# 11-GPS.net
KiCad netlist of a schematic drawn in Altium Designer
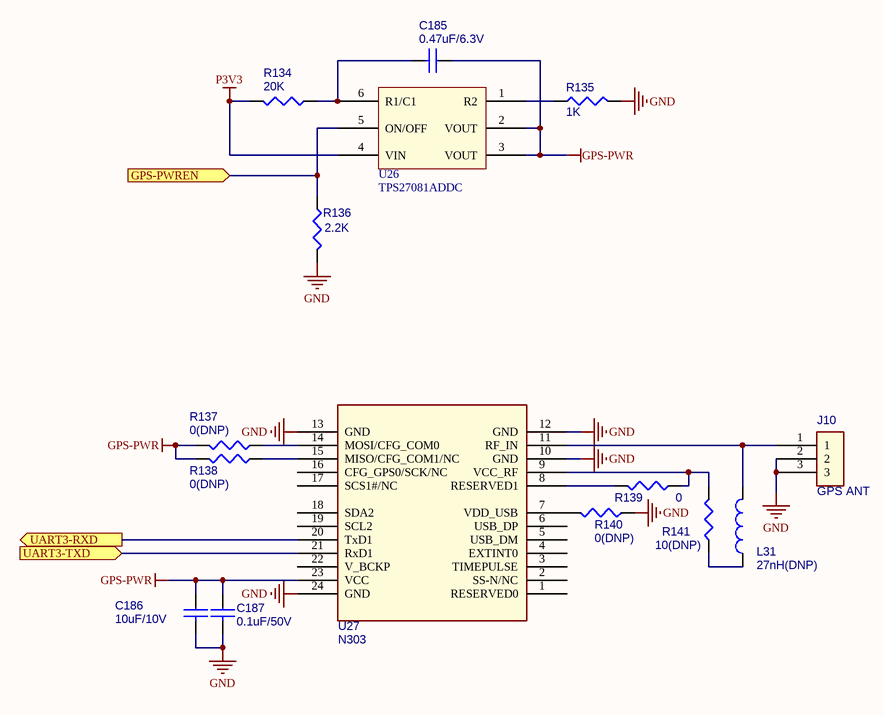
[diagram p0: 11-GPS.SchDoc]

(export (version "E")
  (design (tool "Eeschema 10.0.6"))
  (components
    (comp (ref "C185") (value "0.47uF/6.3V") (footprint "0402") (libsource (lib "*") (part "P_CAP NP")))
    (comp (ref "C186") (value "10uF/10V") (libsource (lib "*") (part "P_CAP NP")))
    (comp (ref "C187") (value "0.1uF/50V") (libsource (lib "*") (part "P_CAP NP")))
    (comp (ref "J10") (value "GPS ANT") (footprint "ANT") (libsource (lib "*") (part "HRS_U_0.FL-R-SMT-10")))
    (comp (ref "L31")
      (value "27nH(DNP)")
      (footprint "0603")
      (libsource (lib "*") (part "2.2UH_LPS3015-222MLC_1.5A_20%~D"))
    )
    (comp (ref "R134") (value "20K") (footprint "0402") (libsource (lib "*") (part "P_R")))
    (comp (ref "R135") (value "1K") (footprint "0402") (libsource (lib "*") (part "P_R")))
    (comp (ref "R136") (value "2.2K") (footprint "0402") (libsource (lib "*") (part "P_R")))
    (comp (ref "R137") (value "0(DNP)") (footprint "0402") (libsource (lib "*") (part "P_R")))
    (comp (ref "R138") (value "0(DNP)") (footprint "0402") (libsource (lib "*") (part "P_R")))
    (comp (ref "R139") (value "0") (footprint "0402") (libsource (lib "*") (part "P_R")))
    (comp (ref "R140") (value "0(DNP)") (footprint "0402") (libsource (lib "*") (part "P_R")))
    (comp (ref "R141") (value "10(DNP)") (footprint "0402") (libsource (lib "*") (part "P_R")))
    (comp (ref "U26")
      (value "TPS27081ADDC")
      (footprint "SOT23-6")
      (libsource (lib "Schlib") (part "TPS27081A"))
    )
    (comp (ref "U27") (value "N303") (footprint "NEO-6") (libsource (lib "*") (part "NEO-5M")))
  )
  (nets
    (net (code "1") (name "/GPS-PWREN") (class "Default")
      (node (ref "R136") (pin "2") (pinfunction "2_2") (pintype "passive"))
      (node (ref "U26") (pin "5") (pinfunction "ON/OFF_5") (pintype "passive"))
    )
    (net (code "2") (name "/UART3-RXD") (class "Default")
      (node (ref "U27") (pin "20") (pinfunction "TxD1_20") (pintype "passive"))
    )
    (net (code "3") (name "/UART3-TXD") (class "Default")
      (node (ref "U27") (pin "21") (pinfunction "RxD1_21") (pintype "passive"))
    )
    (net (code "4") (name "GND") (class "Default")
      (node (ref "C186") (pin "2") (pinfunction "2_2") (pintype "passive"))
      (node (ref "C187") (pin "2") (pinfunction "2_2") (pintype "passive"))
      (node (ref "J10") (pin "2") (pinfunction "2_2") (pintype "passive"))
      (node (ref "J10") (pin "3") (pinfunction "3_3") (pintype "passive"))
      (node (ref "R135") (pin "1") (pinfunction "1_1") (pintype "passive"))
      (node (ref "R136") (pin "1") (pinfunction "1_1") (pintype "passive"))
      (node (ref "R140") (pin "1") (pinfunction "1_1") (pintype "passive"))
      (node (ref "U27") (pin "10") (pinfunction "GND_10") (pintype "power_in"))
      (node (ref "U27") (pin "12") (pinfunction "GND_12") (pintype "power_in"))
      (node (ref "U27") (pin "13") (pinfunction "GND_13") (pintype "power_in"))
      (node (ref "U27") (pin "24") (pinfunction "GND_24") (pintype "power_in"))
    )
    (net (code "5") (name "GPS-PWR") (class "Default")
      (node (ref "C185") (pin "1") (pinfunction "1_1") (pintype "passive"))
      (node (ref "C186") (pin "1") (pinfunction "1_1") (pintype "passive"))
      (node (ref "C187") (pin "1") (pinfunction "1_1") (pintype "passive"))
      (node (ref "R137") (pin "2") (pinfunction "2_2") (pintype "passive"))
      (node (ref "R138") (pin "2") (pinfunction "2_2") (pintype "passive"))
      (node (ref "U26") (pin "2") (pinfunction "VOUT_2") (pintype "passive"))
      (node (ref "U26") (pin "3") (pinfunction "VOUT_3") (pintype "passive"))
      (node (ref "U27") (pin "23") (pinfunction "VCC_23") (pintype "passive"))
    )
    (net (code "6") (name "Net-(L31-Pad1)") (class "Default")
      (node (ref "L31") (pin "1") (pinfunction "1_1") (pintype "passive"))
      (node (ref "R141") (pin "1") (pinfunction "1_1") (pintype "passive"))
    )
    (net (code "7") (name "Net-(U26-R1{slash}C1)") (class "Default")
      (node (ref "C185") (pin "2") (pinfunction "2_2") (pintype "passive"))
      (node (ref "R134") (pin "2") (pinfunction "2_2") (pintype "passive"))
      (node (ref "U26") (pin "6") (pinfunction "R1/C1_6") (pintype "passive"))
    )
    (net (code "8") (name "Net-(U26-R2)") (class "Default")
      (node (ref "R135") (pin "2") (pinfunction "2_2") (pintype "passive"))
      (node (ref "U26") (pin "1") (pinfunction "R2_1") (pintype "passive"))
    )
    (net (code "9") (name "Net-(U27-MISO{slash}CFG_COM1{slash}NC)") (class "Default")
      (node (ref "R138") (pin "1") (pinfunction "1_1") (pintype "passive"))
      (node (ref "U27") (pin "15") (pinfunction "MISO/CFG_COM1/NC_15") (pintype "passive"))
    )
    (net (code "10") (name "Net-(U27-MOSI{slash}CFG_COM0)") (class "Default")
      (node (ref "R137") (pin "1") (pinfunction "1_1") (pintype "passive"))
      (node (ref "U27") (pin "14") (pinfunction "MOSI/CFG_COM0_14") (pintype "passive"))
    )
    (net (code "11") (name "Net-(U27-RESERVED1)") (class "Default")
      (node (ref "R139") (pin "2") (pinfunction "2_2") (pintype "passive"))
      (node (ref "U27") (pin "8") (pinfunction "RESERVED1_8") (pintype "passive"))
    )
    (net (code "12") (name "Net-(U27-RF_IN)") (class "Default")
      (node (ref "J10") (pin "1") (pinfunction "1_1") (pintype "passive"))
      (node (ref "L31") (pin "2") (pinfunction "2_2") (pintype "passive"))
      (node (ref "U27") (pin "11") (pinfunction "RF_IN_11") (pintype "passive"))
    )
    (net (code "13") (name "Net-(U27-VCC_RF)") (class "Default")
      (node (ref "R139") (pin "1") (pinfunction "1_1") (pintype "passive"))
      (node (ref "R141") (pin "2") (pinfunction "2_2") (pintype "passive"))
      (node (ref "U27") (pin "9") (pinfunction "VCC_RF_9") (pintype "passive"))
    )
    (net (code "14") (name "Net-(U27-VDD_USB)") (class "Default")
      (node (ref "R140") (pin "2") (pinfunction "2_2") (pintype "passive"))
      (node (ref "U27") (pin "7") (pinfunction "VDD_USB_7") (pintype "passive"))
    )
    (net (code "15") (name "P3V3") (class "Default")
      (node (ref "R134") (pin "1") (pinfunction "1_1") (pintype "passive"))
      (node (ref "U26") (pin "4") (pinfunction "VIN_4") (pintype "passive"))
    )
    (net (code "16") (name "unconnected-(U27-CFG_GPS0{slash}SCK{slash}NC-Pad16)") (class "Default")
      (node (ref "U27") (pin "16") (pinfunction "CFG_GPS0/SCK/NC_16") (pintype "passive"))
    )
    (net (code "17") (name "unconnected-(U27-EXTINT0-Pad4)") (class "Default")
      (node (ref "U27") (pin "4") (pinfunction "EXTINT0_4") (pintype "passive"))
    )
    (net (code "18") (name "unconnected-(U27-RESERVED0-Pad1)") (class "Default")
      (node (ref "U27") (pin "1") (pinfunction "RESERVED0_1") (pintype "passive"))
    )
    (net (code "19") (name "unconnected-(U27-SCL2-Pad19)") (class "Default")
      (node (ref "U27") (pin "19") (pinfunction "SCL2_19") (pintype "passive"))
    )
    (net (code "20") (name "unconnected-(U27-SCS1#{slash}NC-Pad17)") (class "Default")
      (node (ref "U27") (pin "17") (pinfunction "SCS1#/NC_17") (pintype "passive"))
    )
    (net (code "21") (name "unconnected-(U27-SDA2-Pad18)") (class "Default")
      (node (ref "U27") (pin "18") (pinfunction "SDA2_18") (pintype "passive"))
    )
    (net (code "22") (name "unconnected-(U27-SS-N{slash}NC-Pad2)") (class "Default")
      (node (ref "U27") (pin "2") (pinfunction "SS-N/NC_2") (pintype "passive"))
    )
    (net (code "23") (name "unconnected-(U27-TIMEPULSE-Pad3)") (class "Default")
      (node (ref "U27") (pin "3") (pinfunction "TIMEPULSE_3") (pintype "passive"))
    )
    (net (code "24") (name "unconnected-(U27-USB_DM-Pad5)") (class "Default")
      (node (ref "U27") (pin "5") (pinfunction "USB_DM_5") (pintype "passive"))
    )
    (net (code "25") (name "unconnected-(U27-USB_DP-Pad6)") (class "Default")
      (node (ref "U27") (pin "6") (pinfunction "USB_DP_6") (pintype "passive"))
    )
    (net (code "26") (name "unconnected-(U27-V_BCKP-Pad22)") (class "Default")
      (node (ref "U27") (pin "22") (pinfunction "V_BCKP_22") (pintype "passive"))
    )
  )
)
